# filter-rf.net
KiCad netlist of a schematic drawn in Altium Designer
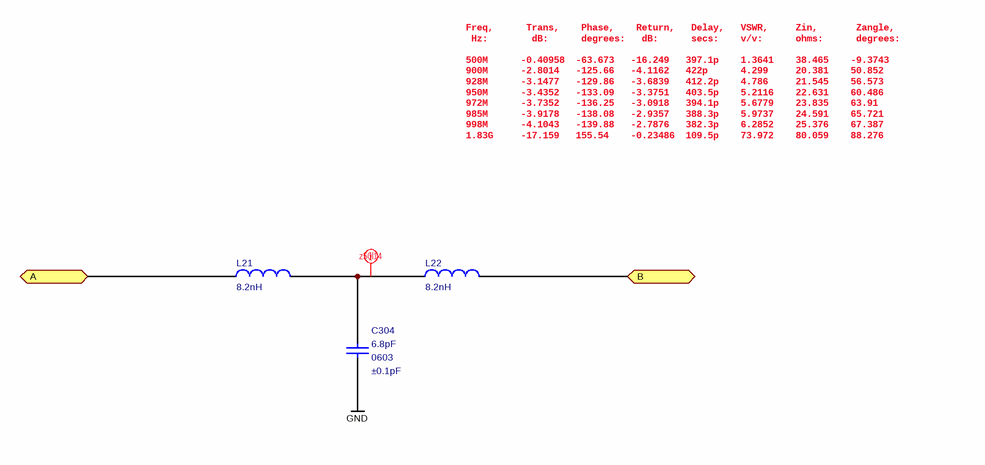
[diagram p0: filter-rf.SchDoc]

(export (version "E")
  (design (tool "Eeschema 10.0.6"))
  (components
    (comp (ref "C304")
      (value "6.8pF")
      (footprint "CAPC160X80X90L20N")
      (description "Ceramic Capacitor 6.8pF ±0.1pF NP0 0603")
      (fields
        (field (name "MANUFACTURER") "AVX")
        (field (name "TOLERANCE") "±0.1pF")
        (field (name "VOLTAGE") "200V")
        (field (name "PACKAGE") "0603")
      )
      (libsource (lib "generic") (part "CAP"))
    )
    (comp (ref "L21")
      (value "8.2nH")
      (footprint "generic:0603")
      (description "Inductor 8.2nH ±2%")
      (fields (field (name "MANUFACTURER") "Murata") (field (name "Comment") "LQW18AN8N2G8ZD"))
      (libsource (lib "generic") (part "INDUCTOR"))
    )
    (comp (ref "L22")
      (value "8.2nH")
      (footprint "generic:0603")
      (description "Inductor 8.2nH ±2%")
      (fields (field (name "MANUFACTURER") "Murata") (field (name "Comment") "LQW18AN8N2G8ZD"))
      (libsource (lib "generic") (part "INDUCTOR"))
    )
  )
  (nets
    (net (code "1") (name "/A") (class "Default")
      (node (ref "L21") (pin "1") (pinfunction "1_1") (pintype "passive"))
    )
    (net (code "2") (name "/B") (class "Default")
      (node (ref "L22") (pin "2") (pinfunction "2_2") (pintype "passive"))
    )
    (net (code "3") (name "GND") (class "Default")
      (node (ref "C304") (pin "1") (pinfunction "1_1") (pintype "passive"))
    )
    (net (code "4") (name "Net-(C304-Pad2)") (class "Default")
      (node (ref "C304") (pin "2") (pinfunction "2_2") (pintype "passive"))
      (node (ref "L21") (pin "2") (pinfunction "2_2") (pintype "passive"))
      (node (ref "L22") (pin "1") (pinfunction "1_1") (pintype "passive"))
    )
  )
)
